# w_projectTQFP2.net
KiCad netlist of a schematic drawn in EAGLE
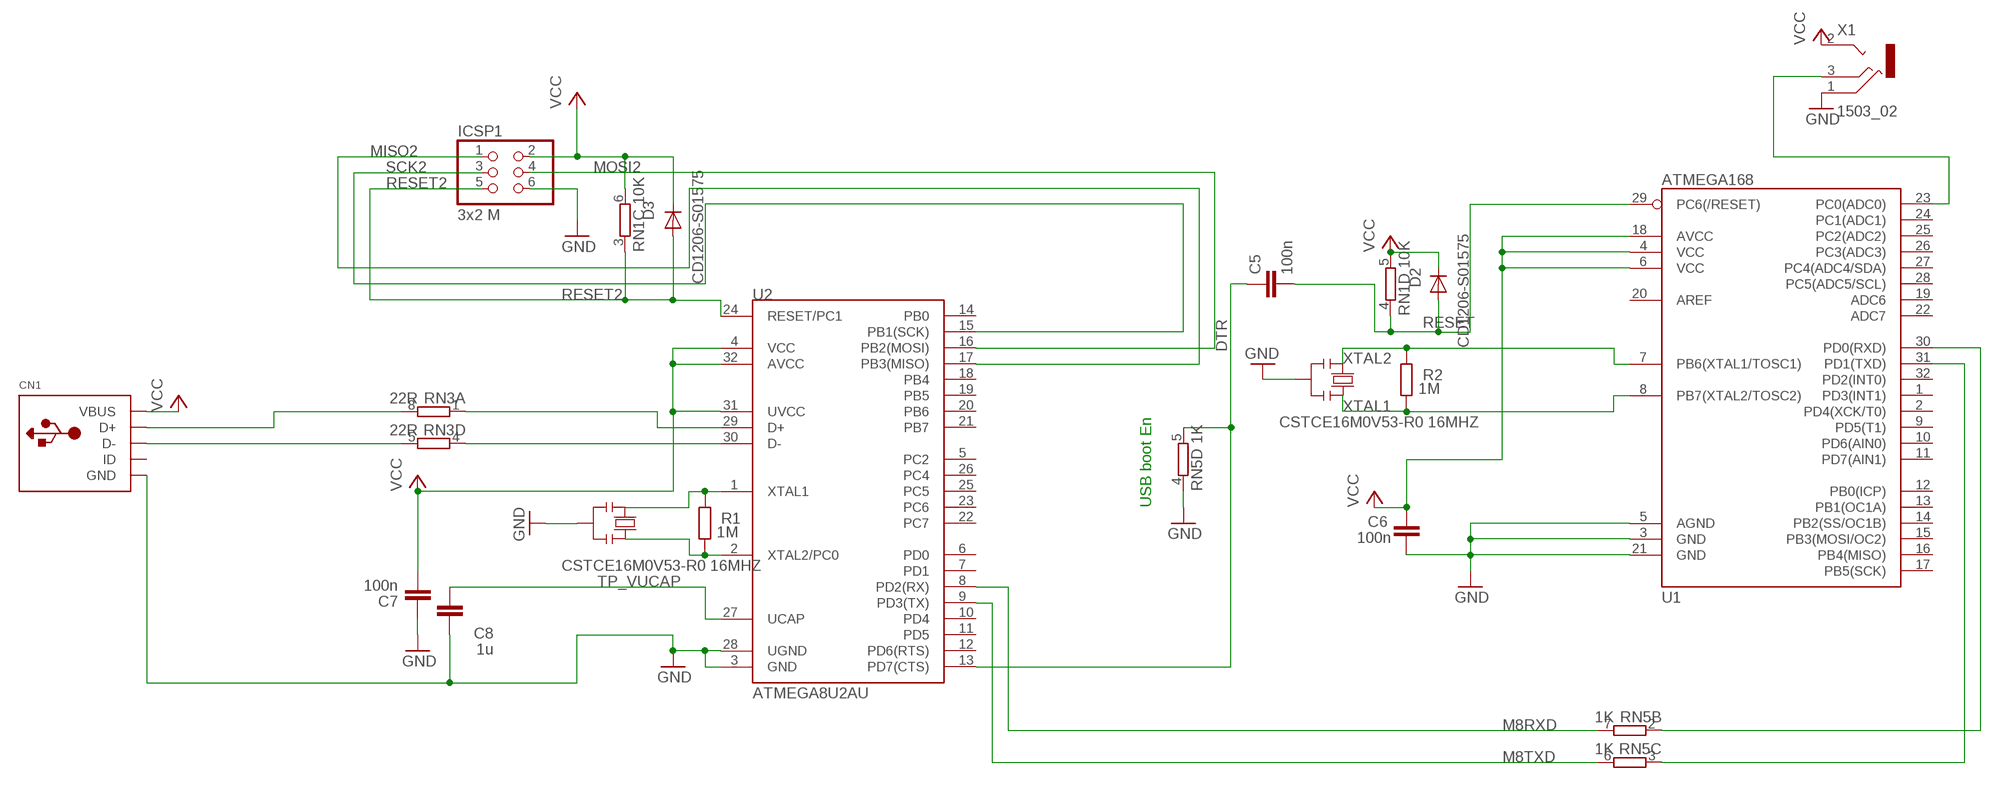
[diagram p0: schematic, sheet 1]

(export (version "E")
  (design (tool "Eeschema 10.0.6"))
  (components
    (comp (ref "C5")
      (value "100n")
      (footprint "eagle-import:C0603-ROUND")
      (fields (field (name "MF") "AVX") (field (name "MPN") "06033G104ZAT2A"))
      (libsource (lib "eagle-import") (part "C-EU0603-RND"))
    )
    (comp (ref "C6")
      (value "100n")
      (footprint "eagle-import:C0603-ROUND")
      (fields (field (name "MF") "AVX") (field (name "MPN") "06033G104ZAT2A"))
      (libsource (lib "eagle-import") (part "C-EU0603-RND"))
    )
    (comp (ref "C7")
      (value "100n")
      (footprint "eagle-import:C0603-ROUND")
      (fields (field (name "MF") "AVX") (field (name "MPN") "06033G104ZAT2A"))
      (libsource (lib "eagle-import") (part "C-EU0603-RND"))
    )
    (comp (ref "C8")
      (value "1u")
      (footprint "eagle-import:C0603-ROUND")
      (fields (field (name "MF") "AVX") (field (name "MPN") "1206YC105KAT2A"))
      (libsource (lib "eagle-import") (part "C-EU0603-RND"))
    )
    (comp (ref "CN1")
      (value "USBMINIB")
      (footprint "eagle-import:USB-MINIB")
      (fields (field (name "MF") "MOLEX") (field (name "MPN") "67503-1030"))
      (libsource (lib "eagle-import") (part "USBMINIB"))
    )
    (comp (ref "D2")
      (value "CD1206-S01575")
      (footprint "eagle-import:MINIMELF")
      (fields (field (name "MF") "BOURNS"))
      (libsource (lib "eagle-import") (part "DIODE-MINIMELF"))
    )
    (comp (ref "D3")
      (value "CD1206-S01575")
      (footprint "eagle-import:MINIMELF")
      (fields (field (name "MF") "BOURNS"))
      (libsource (lib "eagle-import") (part "DIODE-MINIMELF"))
    )
    (comp (ref "ICSP1")
      (value "3x2 M")
      (footprint "eagle-import:2X03")
      (libsource (lib "eagle-import") (part "PINHD-2X3"))
    )
    (comp (ref "R1")
      (value "1M")
      (footprint "eagle-import:R0603-ROUND")
      (fields (field (name "MF") "BOURNS") (field (name "MPN") "CR0603-JW-105GLF"))
      (libsource (lib "eagle-import") (part "R-EU_R0603"))
    )
    (comp (ref "R2")
      (value "1M")
      (footprint "eagle-import:R0603-ROUND")
      (fields (field (name "MF") "BOURNS") (field (name "MPN") "CR0603-JW-105GLF"))
      (libsource (lib "eagle-import") (part "R-EU_R0603"))
    )
    (comp (ref "RN1")
      (value "10K")
      (footprint "eagle-import:CAY16")
      (fields
        (field (name "MF") "BOURNS")
        (field (name "MPN") "CAY16-1002F4LF.")
        (field (name "OC_FARNELL") "1768294")
      )
      (libsource (lib "eagle-import") (part "4R-NCAY16"))
    )
    (comp (ref "RN3")
      (value "22R")
      (footprint "eagle-import:CAY16")
      (fields
        (field (name "MF") "BOURNS")
        (field (name "MPN") "CAY16-220J4LF")
        (field (name "OC_FARNELL") "1770127")
      )
      (libsource (lib "eagle-import") (part "4R-NCAY16"))
    )
    (comp (ref "RN5")
      (value "1K")
      (footprint "eagle-import:CAY16")
      (fields
        (field (name "MF") "BOURNS")
        (field (name "MPN") "CAY16-102J4LF")
        (field (name "OC_FARNELL") "1553319")
      )
      (libsource (lib "eagle-import") (part "4R-NCAY16"))
    )
    (comp (ref "U1")
      (value "ATMEGA168")
      (footprint "eagle-import:TQFP32-08")
      (fields (field (name "MF") "ATMEL") (field (name "MPN") "ATMEGA328P-AU"))
      (libsource (lib "eagle-import") (part "ATMEGA168"))
    )
    (comp (ref "U2")
      (value "ATMEGA8U2AU")
      (footprint "eagle-import:TQFP32-08")
      (fields (field (name "MF") "ATMEL") (field (name "MPN") "ATMEGA16U2-AU"))
      (libsource (lib "eagle-import") (part "ATMEGA8U2AU"))
    )
    (comp (ref "X1")
      (value "1503_02")
      (footprint "eagle-import:1503_02")
      (fields
        (field (name "MF") "LUMBERG")
        (field (name "MPN") "1503 02")
        (field (name "OC_FARNELL") "1216979")
      )
      (libsource (lib "eagle-import") (part "1503_02"))
    )
    (comp (ref "Y2")
      (value "CSTCE16M0V53-R0 16MHZ")
      (footprint "eagle-import:RESONATOR")
      (fields (field (name "MF") "MURATA") (field (name "MPN") "CSTCE16M0V53-R0"))
      (libsource (lib "eagle-import") (part "RESONATORMU"))
    )
    (comp (ref "Y4")
      (value "CSTCE16M0V53-R0 16MHZ")
      (footprint "eagle-import:RESONATOR")
      (fields (field (name "MF") "MURATA") (field (name "MPN") "CSTCE16M0V53-R0"))
      (libsource (lib "eagle-import") (part "RESONATORMU"))
    )
  )
  (nets
    (net (code "1") (name "/DTR") (class "Default")
      (node (ref "C5") (pin "1") (pinfunction "1_1") (pintype "passive"))
      (node (ref "RN5") (pin "5") (pinfunction "2_5") (pintype "passive"))
      (node (ref "U2") (pin "13") (pinfunction "PD7(CTS)_13") (pintype "bidirectional"))
    )
    (net (code "2") (name "/M8RXD") (class "Default")
      (node (ref "RN5") (pin "7") (pinfunction "2_7") (pintype "passive"))
      (node (ref "U2") (pin "8") (pinfunction "PD2(RX)_8") (pintype "bidirectional"))
    )
    (net (code "3") (name "/M8TXD") (class "Default")
      (node (ref "RN5") (pin "6") (pinfunction "2_6") (pintype "passive"))
      (node (ref "U2") (pin "9") (pinfunction "PD3(TX)_9") (pintype "bidirectional"))
    )
    (net (code "4") (name "/MISO2") (class "Default")
      (node (ref "ICSP1") (pin "1") (pinfunction "1_1") (pintype "passive"))
      (node (ref "U2") (pin "17") (pinfunction "PB3(MISO)_17") (pintype "bidirectional"))
    )
    (net (code "5") (name "/MOSI2") (class "Default")
      (node (ref "ICSP1") (pin "4") (pinfunction "4_4") (pintype "passive"))
      (node (ref "U2") (pin "16") (pinfunction "PB2(MOSI)_16") (pintype "bidirectional"))
    )
    (net (code "6") (name "/RESET") (class "Default")
      (node (ref "C5") (pin "2") (pinfunction "2_2") (pintype "passive"))
      (node (ref "D2") (pin "A") (pinfunction "A_A") (pintype "passive"))
      (node (ref "RN1") (pin "4") (pinfunction "1_4") (pintype "passive"))
      (node (ref "U1") (pin "29") (pinfunction "PC6(/RESET)_29") (pintype "bidirectional"))
    )
    (net (code "7") (name "/RESET2") (class "Default")
      (node (ref "D3") (pin "A") (pinfunction "A_A") (pintype "passive"))
      (node (ref "ICSP1") (pin "5") (pinfunction "5_5") (pintype "passive"))
      (node (ref "RN1") (pin "3") (pinfunction "1_3") (pintype "passive"))
      (node (ref "U2") (pin "24") (pinfunction "RESET/PC1_24") (pintype "bidirectional"))
    )
    (net (code "8") (name "/SCK2") (class "Default")
      (node (ref "ICSP1") (pin "3") (pinfunction "3_3") (pintype "passive"))
      (node (ref "U2") (pin "15") (pinfunction "PB1(SCK)_15") (pintype "bidirectional"))
    )
    (net (code "9") (name "/TP_VUCAP") (class "Default")
      (node (ref "C8") (pin "1") (pinfunction "1_1") (pintype "passive"))
      (node (ref "U2") (pin "27") (pinfunction "UCAP_27") (pintype "bidirectional"))
    )
    (net (code "10") (name "/XTAL1") (class "Default")
      (node (ref "R2") (pin "1") (pinfunction "1_1") (pintype "passive"))
      (node (ref "U1") (pin "8") (pinfunction "PB7(XTAL2/TOSC2)_8") (pintype "bidirectional"))
      (node (ref "Y2") (pin "3") (pinfunction "3_3") (pintype "passive"))
    )
    (net (code "11") (name "/XTAL2") (class "Default")
      (node (ref "R2") (pin "2") (pinfunction "2_2") (pintype "passive"))
      (node (ref "U1") (pin "7") (pinfunction "PB6(XTAL1/TOSC1)_7") (pintype "bidirectional"))
      (node (ref "Y2") (pin "1") (pinfunction "1_1") (pintype "passive"))
    )
    (net (code "12") (name "GND") (class "Default")
      (node (ref "C6") (pin "1") (pinfunction "1_1") (pintype "passive"))
      (node (ref "C7") (pin "2") (pinfunction "2_2") (pintype "passive"))
      (node (ref "C8") (pin "2") (pinfunction "2_2") (pintype "passive"))
      (node (ref "CN1") (pin "GND") (pinfunction "GND_GND") (pintype "power_in"))
      (node (ref "ICSP1") (pin "6") (pinfunction "6_6") (pintype "passive"))
      (node (ref "RN5") (pin "4") (pinfunction "1_4") (pintype "passive"))
      (node (ref "U1") (pin "21") (pinfunction "GND_21") (pintype "bidirectional"))
      (node (ref "U1") (pin "3") (pinfunction "GND_3") (pintype "bidirectional"))
      (node (ref "U1") (pin "5") (pinfunction "AGND_5") (pintype "bidirectional"))
      (node (ref "U2") (pin "28") (pinfunction "UGND_28") (pintype "bidirectional"))
      (node (ref "U2") (pin "3") (pinfunction "GND_3") (pintype "bidirectional"))
      (node (ref "X1") (pin "1") (pinfunction "1_1") (pintype "passive"))
      (node (ref "Y2") (pin "2") (pinfunction "2_2") (pintype "passive"))
      (node (ref "Y4") (pin "2") (pinfunction "2_2") (pintype "passive"))
    )
    (net (code "13") (name "Net-(RN3A-2)") (class "Default")
      (node (ref "CN1") (pin "D+") (pinfunction "D+_D+") (pintype "bidirectional"))
      (node (ref "RN3") (pin "8") (pinfunction "2_8") (pintype "passive"))
    )
    (net (code "14") (name "Net-(RN3D-1)") (class "Default")
      (node (ref "RN3") (pin "4") (pinfunction "1_4") (pintype "passive"))
      (node (ref "U2") (pin "30") (pinfunction "D-_30") (pintype "bidirectional"))
    )
    (net (code "15") (name "Net-(RN3D-2)") (class "Default")
      (node (ref "CN1") (pin "D-") (pinfunction "D-_D-") (pintype "bidirectional"))
      (node (ref "RN3") (pin "5") (pinfunction "2_5") (pintype "passive"))
    )
    (net (code "16") (name "Net-(RN5B-1)") (class "Default")
      (node (ref "RN5") (pin "2") (pinfunction "1_2") (pintype "passive"))
      (node (ref "U1") (pin "30") (pinfunction "PD0(RXD)_30") (pintype "bidirectional"))
    )
    (net (code "17") (name "Net-(RN5C-1)") (class "Default")
      (node (ref "RN5") (pin "3") (pinfunction "1_3") (pintype "passive"))
      (node (ref "U1") (pin "31") (pinfunction "PD1(TXD)_31") (pintype "bidirectional"))
    )
    (net (code "18") (name "Net-(U1-PC0(ADC0))") (class "Default")
      (node (ref "U1") (pin "23") (pinfunction "PC0(ADC0)_23") (pintype "bidirectional"))
      (node (ref "X1") (pin "3") (pinfunction "3_3") (pintype "passive"))
    )
    (net (code "19") (name "Net-(U2-D+)") (class "Default")
      (node (ref "RN3") (pin "1") (pinfunction "1_1") (pintype "passive"))
      (node (ref "U2") (pin "29") (pinfunction "D+_29") (pintype "bidirectional"))
    )
    (net (code "20") (name "Net-(U2-XTAL1)") (class "Default")
      (node (ref "R1") (pin "2") (pinfunction "2_2") (pintype "passive"))
      (node (ref "U2") (pin "1") (pinfunction "XTAL1_1") (pintype "bidirectional"))
      (node (ref "Y4") (pin "1") (pinfunction "1_1") (pintype "passive"))
    )
    (net (code "21") (name "Net-(U2-XTAL2{slash}PC0)") (class "Default")
      (node (ref "R1") (pin "1") (pinfunction "1_1") (pintype "passive"))
      (node (ref "U2") (pin "2") (pinfunction "XTAL2/PC0_2") (pintype "bidirectional"))
      (node (ref "Y4") (pin "3") (pinfunction "3_3") (pintype "passive"))
    )
    (net (code "22") (name "VCC") (class "Default")
      (node (ref "C6") (pin "2") (pinfunction "2_2") (pintype "passive"))
      (node (ref "C7") (pin "1") (pinfunction "1_1") (pintype "passive"))
      (node (ref "CN1") (pin "VBUS") (pinfunction "VBUS_VBUS") (pintype "power_in"))
      (node (ref "D2") (pin "C") (pinfunction "C_C") (pintype "passive"))
      (node (ref "D3") (pin "C") (pinfunction "C_C") (pintype "passive"))
      (node (ref "ICSP1") (pin "2") (pinfunction "2_2") (pintype "passive"))
      (node (ref "RN1") (pin "5") (pinfunction "2_5") (pintype "passive"))
      (node (ref "RN1") (pin "6") (pinfunction "2_6") (pintype "passive"))
      (node (ref "U1") (pin "18") (pinfunction "AVCC_18") (pintype "bidirectional"))
      (node (ref "U1") (pin "4") (pinfunction "VCC_4") (pintype "bidirectional"))
      (node (ref "U1") (pin "6") (pinfunction "VCC_6") (pintype "bidirectional"))
      (node (ref "U2") (pin "31") (pinfunction "UVCC_31") (pintype "bidirectional"))
      (node (ref "U2") (pin "32") (pinfunction "AVCC_32") (pintype "bidirectional"))
      (node (ref "U2") (pin "4") (pinfunction "VCC_4") (pintype "bidirectional"))
      (node (ref "X1") (pin "2") (pinfunction "2_2") (pintype "passive"))
    )
    (net (code "23") (name "unconnected-(CN1-PadID)") (class "Default")
      (node (ref "CN1") (pin "ID") (pinfunction "ID_ID") (pintype "bidirectional"))
    )
    (net (code "24") (name "unconnected-(U1-ADC6-Pad19)") (class "Default")
      (node (ref "U1") (pin "19") (pinfunction "ADC6_19") (pintype "bidirectional"))
    )
    (net (code "25") (name "unconnected-(U1-ADC7-Pad22)") (class "Default")
      (node (ref "U1") (pin "22") (pinfunction "ADC7_22") (pintype "bidirectional"))
    )
    (net (code "26") (name "unconnected-(U1-AREF-Pad20)") (class "Default")
      (node (ref "U1") (pin "20") (pinfunction "AREF_20") (pintype "bidirectional"))
    )
    (net (code "27") (name "unconnected-(U1-PB0(ICP)-Pad12)") (class "Default")
      (node (ref "U1") (pin "12") (pinfunction "PB0(ICP)_12") (pintype "bidirectional"))
    )
    (net (code "28") (name "unconnected-(U1-PB1(OC1A)-Pad13)") (class "Default")
      (node (ref "U1") (pin "13") (pinfunction "PB1(OC1A)_13") (pintype "bidirectional"))
    )
    (net (code "29") (name "unconnected-(U1-PB2(SS{slash}OC1B)-Pad14)") (class "Default")
      (node (ref "U1") (pin "14") (pinfunction "PB2(SS/OC1B)_14") (pintype "bidirectional"))
    )
    (net (code "30") (name "unconnected-(U1-PB3(MOSI{slash}OC2)-Pad15)") (class "Default")
      (node (ref "U1") (pin "15") (pinfunction "PB3(MOSI/OC2)_15") (pintype "bidirectional"))
    )
    (net (code "31") (name "unconnected-(U1-PB4(MISO)-Pad16)") (class "Default")
      (node (ref "U1") (pin "16") (pinfunction "PB4(MISO)_16") (pintype "bidirectional"))
    )
    (net (code "32") (name "unconnected-(U1-PB5(SCK)-Pad17)") (class "Default")
      (node (ref "U1") (pin "17") (pinfunction "PB5(SCK)_17") (pintype "bidirectional"))
    )
    (net (code "33") (name "unconnected-(U1-PC1(ADC1)-Pad24)") (class "Default")
      (node (ref "U1") (pin "24") (pinfunction "PC1(ADC1)_24") (pintype "bidirectional"))
    )
    (net (code "34") (name "unconnected-(U1-PC2(ADC2)-Pad25)") (class "Default")
      (node (ref "U1") (pin "25") (pinfunction "PC2(ADC2)_25") (pintype "bidirectional"))
    )
    (net (code "35") (name "unconnected-(U1-PC3(ADC3)-Pad26)") (class "Default")
      (node (ref "U1") (pin "26") (pinfunction "PC3(ADC3)_26") (pintype "bidirectional"))
    )
    (net (code "36") (name "unconnected-(U1-PC4(ADC4{slash}SDA)-Pad27)") (class "Default")
      (node (ref "U1") (pin "27") (pinfunction "PC4(ADC4/SDA)_27") (pintype "bidirectional"))
    )
    (net (code "37") (name "unconnected-(U1-PC5(ADC5{slash}SCL)-Pad28)") (class "Default")
      (node (ref "U1") (pin "28") (pinfunction "PC5(ADC5/SCL)_28") (pintype "bidirectional"))
    )
    (net (code "38") (name "unconnected-(U1-PD2(INT0)-Pad32)") (class "Default")
      (node (ref "U1") (pin "32") (pinfunction "PD2(INT0)_32") (pintype "bidirectional"))
    )
    (net (code "39") (name "unconnected-(U1-PD3(INT1)-Pad1)") (class "Default")
      (node (ref "U1") (pin "1") (pinfunction "PD3(INT1)_1") (pintype "bidirectional"))
    )
    (net (code "40") (name "unconnected-(U1-PD4(XCK{slash}T0)-Pad2)") (class "Default")
      (node (ref "U1") (pin "2") (pinfunction "PD4(XCK/T0)_2") (pintype "bidirectional"))
    )
    (net (code "41") (name "unconnected-(U1-PD5(T1)-Pad9)") (class "Default")
      (node (ref "U1") (pin "9") (pinfunction "PD5(T1)_9") (pintype "bidirectional"))
    )
    (net (code "42") (name "unconnected-(U1-PD6(AIN0)-Pad10)") (class "Default")
      (node (ref "U1") (pin "10") (pinfunction "PD6(AIN0)_10") (pintype "bidirectional"))
    )
    (net (code "43") (name "unconnected-(U1-PD7(AIN1)-Pad11)") (class "Default")
      (node (ref "U1") (pin "11") (pinfunction "PD7(AIN1)_11") (pintype "bidirectional"))
    )
    (net (code "44") (name "unconnected-(U2-PB0-Pad14)") (class "Default")
      (node (ref "U2") (pin "14") (pinfunction "PB0_14") (pintype "bidirectional"))
    )
    (net (code "45") (name "unconnected-(U2-PB4-Pad18)") (class "Default")
      (node (ref "U2") (pin "18") (pinfunction "PB4_18") (pintype "bidirectional"))
    )
    (net (code "46") (name "unconnected-(U2-PB5-Pad19)") (class "Default")
      (node (ref "U2") (pin "19") (pinfunction "PB5_19") (pintype "bidirectional"))
    )
    (net (code "47") (name "unconnected-(U2-PB6-Pad20)") (class "Default")
      (node (ref "U2") (pin "20") (pinfunction "PB6_20") (pintype "bidirectional"))
    )
    (net (code "48") (name "unconnected-(U2-PB7-Pad21)") (class "Default")
      (node (ref "U2") (pin "21") (pinfunction "PB7_21") (pintype "bidirectional"))
    )
    (net (code "49") (name "unconnected-(U2-PC2-Pad5)") (class "Default")
      (node (ref "U2") (pin "5") (pinfunction "PC2_5") (pintype "bidirectional"))
    )
    (net (code "50") (name "unconnected-(U2-PC4-Pad26)") (class "Default")
      (node (ref "U2") (pin "26") (pinfunction "PC4_26") (pintype "bidirectional"))
    )
    (net (code "51") (name "unconnected-(U2-PC5-Pad25)") (class "Default")
      (node (ref "U2") (pin "25") (pinfunction "PC5_25") (pintype "bidirectional"))
    )
    (net (code "52") (name "unconnected-(U2-PC6-Pad23)") (class "Default")
      (node (ref "U2") (pin "23") (pinfunction "PC6_23") (pintype "bidirectional"))
    )
    (net (code "53") (name "unconnected-(U2-PC7-Pad22)") (class "Default")
      (node (ref "U2") (pin "22") (pinfunction "PC7_22") (pintype "bidirectional"))
    )
    (net (code "54") (name "unconnected-(U2-PD0-Pad6)") (class "Default")
      (node (ref "U2") (pin "6") (pinfunction "PD0_6") (pintype "bidirectional"))
    )
    (net (code "55") (name "unconnected-(U2-PD1-Pad7)") (class "Default")
      (node (ref "U2") (pin "7") (pinfunction "PD1_7") (pintype "bidirectional"))
    )
    (net (code "56") (name "unconnected-(U2-PD4-Pad10)") (class "Default")
      (node (ref "U2") (pin "10") (pinfunction "PD4_10") (pintype "bidirectional"))
    )
    (net (code "57") (name "unconnected-(U2-PD5-Pad11)") (class "Default")
      (node (ref "U2") (pin "11") (pinfunction "PD5_11") (pintype "bidirectional"))
    )
    (net (code "58") (name "unconnected-(U2-PD6(RTS)-Pad12)") (class "Default")
      (node (ref "U2") (pin "12") (pinfunction "PD6(RTS)_12") (pintype "bidirectional"))
    )
    (net (code "59") (name "unconnected-(X1-2-Pad2@2)") (class "Default")
      (node (ref "X1") (pin "2@2") (pinfunction "2_2@2") (pintype "passive"))
    )
  )
)
